# MaximAnalogSignalInterface.net
KiCad netlist of a schematic drawn in Altium Designer
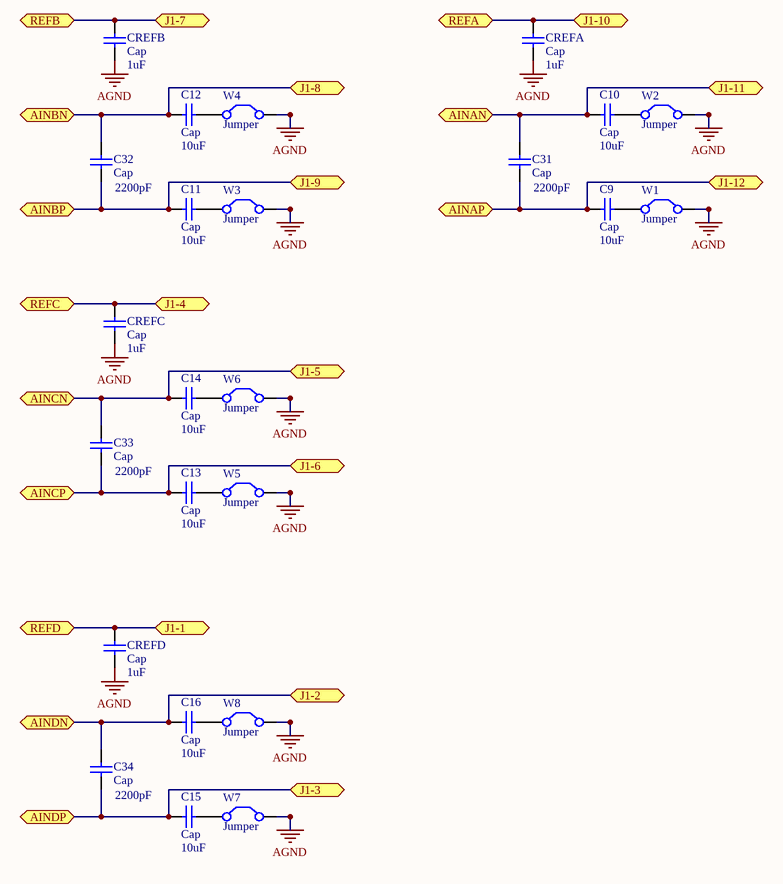
[diagram p0: MaximAnalogSignalInterface.SchDoc]

(export (version "E")
  (design (tool "Eeschema 10.0.6"))
  (components
    (comp (ref "C9")
      (value "Cap")
      (footprint "RAD-0.3")
      (description "Capacitor")
      (fields (field (name "ALTIUM_VALUE") "10uF") (field (name "PUBLISHER") "Altium Limited"))
      (libsource (lib "Miscellaneous Devices") (part "Cap"))
    )
    (comp (ref "C10")
      (value "Cap")
      (footprint "RAD-0.3")
      (description "Capacitor")
      (fields (field (name "ALTIUM_VALUE") "10uF") (field (name "PUBLISHER") "Altium Limited"))
      (libsource (lib "Miscellaneous Devices") (part "Cap"))
    )
    (comp (ref "C11")
      (value "Cap")
      (footprint "RAD-0.3")
      (description "Capacitor")
      (fields (field (name "ALTIUM_VALUE") "10uF") (field (name "PUBLISHER") "Altium Limited"))
      (libsource (lib "Miscellaneous Devices") (part "Cap"))
    )
    (comp (ref "C12")
      (value "Cap")
      (footprint "RAD-0.3")
      (description "Capacitor")
      (fields (field (name "ALTIUM_VALUE") "10uF") (field (name "PUBLISHER") "Altium Limited"))
      (libsource (lib "Miscellaneous Devices") (part "Cap"))
    )
    (comp (ref "C13")
      (value "Cap")
      (footprint "RAD-0.3")
      (description "Capacitor")
      (fields (field (name "ALTIUM_VALUE") "10uF") (field (name "PUBLISHER") "Altium Limited"))
      (libsource (lib "Miscellaneous Devices") (part "Cap"))
    )
    (comp (ref "C14")
      (value "Cap")
      (footprint "RAD-0.3")
      (description "Capacitor")
      (fields (field (name "ALTIUM_VALUE") "10uF") (field (name "PUBLISHER") "Altium Limited"))
      (libsource (lib "Miscellaneous Devices") (part "Cap"))
    )
    (comp (ref "C15")
      (value "Cap")
      (footprint "RAD-0.3")
      (description "Capacitor")
      (fields (field (name "ALTIUM_VALUE") "10uF") (field (name "PUBLISHER") "Altium Limited"))
      (libsource (lib "Miscellaneous Devices") (part "Cap"))
    )
    (comp (ref "C16")
      (value "Cap")
      (footprint "RAD-0.3")
      (description "Capacitor")
      (fields (field (name "ALTIUM_VALUE") "10uF") (field (name "PUBLISHER") "Altium Limited"))
      (libsource (lib "Miscellaneous Devices") (part "Cap"))
    )
    (comp (ref "C31")
      (value "Cap")
      (footprint "RAD-0.3")
      (description "Capacitor")
      (fields (field (name "ALTIUM_VALUE") "2200pF") (field (name "PUBLISHER") "Altium Limited"))
      (libsource (lib "Miscellaneous Devices") (part "Cap"))
    )
    (comp (ref "C32")
      (value "Cap")
      (footprint "RAD-0.3")
      (description "Capacitor")
      (fields (field (name "ALTIUM_VALUE") "2200pF") (field (name "PUBLISHER") "Altium Limited"))
      (libsource (lib "Miscellaneous Devices") (part "Cap"))
    )
    (comp (ref "C33")
      (value "Cap")
      (footprint "RAD-0.3")
      (description "Capacitor")
      (fields (field (name "ALTIUM_VALUE") "2200pF") (field (name "PUBLISHER") "Altium Limited"))
      (libsource (lib "Miscellaneous Devices") (part "Cap"))
    )
    (comp (ref "C34")
      (value "Cap")
      (footprint "RAD-0.3")
      (description "Capacitor")
      (fields (field (name "ALTIUM_VALUE") "2200pF") (field (name "PUBLISHER") "Altium Limited"))
      (libsource (lib "Miscellaneous Devices") (part "Cap"))
    )
    (comp (ref "CREFA")
      (value "Cap")
      (footprint "RAD-0.3")
      (description "Capacitor")
      (fields (field (name "ALTIUM_VALUE") "1uF") (field (name "PUBLISHER") "Altium Limited"))
      (libsource (lib "Miscellaneous Devices") (part "Cap"))
    )
    (comp (ref "CREFB")
      (value "Cap")
      (footprint "RAD-0.3")
      (description "Capacitor")
      (fields (field (name "ALTIUM_VALUE") "1uF") (field (name "PUBLISHER") "Altium Limited"))
      (libsource (lib "Miscellaneous Devices") (part "Cap"))
    )
    (comp (ref "CREFC")
      (value "Cap")
      (footprint "RAD-0.3")
      (description "Capacitor")
      (fields (field (name "ALTIUM_VALUE") "1uF") (field (name "PUBLISHER") "Altium Limited"))
      (libsource (lib "Miscellaneous Devices") (part "Cap"))
    )
    (comp (ref "CREFD")
      (value "Cap")
      (footprint "RAD-0.3")
      (description "Capacitor")
      (fields (field (name "ALTIUM_VALUE") "1uF") (field (name "PUBLISHER") "Altium Limited"))
      (libsource (lib "Miscellaneous Devices") (part "Cap"))
    )
    (comp (ref "W1")
      (value "Jumper")
      (footprint "RAD-0.2")
      (description "Jumper Wire")
      (fields (field (name "PUBLISHER") "Altium Limited"))
      (libsource (lib "Miscellaneous Devices") (part "Jumper"))
    )
    (comp (ref "W2")
      (value "Jumper")
      (footprint "RAD-0.2")
      (description "Jumper Wire")
      (fields (field (name "PUBLISHER") "Altium Limited"))
      (libsource (lib "Miscellaneous Devices") (part "Jumper"))
    )
    (comp (ref "W3")
      (value "Jumper")
      (footprint "RAD-0.2")
      (description "Jumper Wire")
      (fields (field (name "PUBLISHER") "Altium Limited"))
      (libsource (lib "Miscellaneous Devices") (part "Jumper"))
    )
    (comp (ref "W4")
      (value "Jumper")
      (footprint "RAD-0.2")
      (description "Jumper Wire")
      (fields (field (name "PUBLISHER") "Altium Limited"))
      (libsource (lib "Miscellaneous Devices") (part "Jumper"))
    )
    (comp (ref "W5")
      (value "Jumper")
      (footprint "RAD-0.2")
      (description "Jumper Wire")
      (fields (field (name "PUBLISHER") "Altium Limited"))
      (libsource (lib "Miscellaneous Devices") (part "Jumper"))
    )
    (comp (ref "W6")
      (value "Jumper")
      (footprint "RAD-0.2")
      (description "Jumper Wire")
      (fields (field (name "PUBLISHER") "Altium Limited"))
      (libsource (lib "Miscellaneous Devices") (part "Jumper"))
    )
    (comp (ref "W7")
      (value "Jumper")
      (footprint "RAD-0.2")
      (description "Jumper Wire")
      (fields (field (name "PUBLISHER") "Altium Limited"))
      (libsource (lib "Miscellaneous Devices") (part "Jumper"))
    )
    (comp (ref "W8")
      (value "Jumper")
      (footprint "RAD-0.2")
      (description "Jumper Wire")
      (fields (field (name "PUBLISHER") "Altium Limited"))
      (libsource (lib "Miscellaneous Devices") (part "Jumper"))
    )
  )
  (nets
    (net (code "1") (name "/AINAN") (class "Default")
      (node (ref "C10") (pin "2") (pinfunction "2_2") (pintype "passive"))
      (node (ref "C31") (pin "2") (pinfunction "2_2") (pintype "passive"))
    )
    (net (code "2") (name "/AINAP") (class "Default")
      (node (ref "C31") (pin "1") (pinfunction "1_1") (pintype "passive"))
      (node (ref "C9") (pin "2") (pinfunction "2_2") (pintype "passive"))
    )
    (net (code "3") (name "/AINBN") (class "Default")
      (node (ref "C12") (pin "2") (pinfunction "2_2") (pintype "passive"))
      (node (ref "C32") (pin "2") (pinfunction "2_2") (pintype "passive"))
    )
    (net (code "4") (name "/AINBP") (class "Default")
      (node (ref "C11") (pin "2") (pinfunction "2_2") (pintype "passive"))
      (node (ref "C32") (pin "1") (pinfunction "1_1") (pintype "passive"))
    )
    (net (code "5") (name "/AINCN") (class "Default")
      (node (ref "C14") (pin "2") (pinfunction "2_2") (pintype "passive"))
      (node (ref "C33") (pin "2") (pinfunction "2_2") (pintype "passive"))
    )
    (net (code "6") (name "/AINCP") (class "Default")
      (node (ref "C13") (pin "2") (pinfunction "2_2") (pintype "passive"))
      (node (ref "C33") (pin "1") (pinfunction "1_1") (pintype "passive"))
    )
    (net (code "7") (name "/AINDN") (class "Default")
      (node (ref "C16") (pin "2") (pinfunction "2_2") (pintype "passive"))
      (node (ref "C34") (pin "2") (pinfunction "2_2") (pintype "passive"))
    )
    (net (code "8") (name "/AINDP") (class "Default")
      (node (ref "C15") (pin "2") (pinfunction "2_2") (pintype "passive"))
      (node (ref "C34") (pin "1") (pinfunction "1_1") (pintype "passive"))
    )
    (net (code "9") (name "/J1-1") (class "Default")
      (node (ref "CREFD") (pin "2") (pinfunction "2_2") (pintype "passive"))
    )
    (net (code "10") (name "/J1-4") (class "Default")
      (node (ref "CREFC") (pin "2") (pinfunction "2_2") (pintype "passive"))
    )
    (net (code "11") (name "/J1-7") (class "Default")
      (node (ref "CREFB") (pin "2") (pinfunction "2_2") (pintype "passive"))
    )
    (net (code "12") (name "/J1-10") (class "Default")
      (node (ref "CREFA") (pin "2") (pinfunction "2_2") (pintype "passive"))
    )
    (net (code "13") (name "AGND") (class "Default")
      (node (ref "CREFA") (pin "1") (pinfunction "1_1") (pintype "passive"))
      (node (ref "CREFB") (pin "1") (pinfunction "1_1") (pintype "passive"))
      (node (ref "CREFC") (pin "1") (pinfunction "1_1") (pintype "passive"))
      (node (ref "CREFD") (pin "1") (pinfunction "1_1") (pintype "passive"))
      (node (ref "W1") (pin "2") (pinfunction "C2_2") (pintype "passive"))
      (node (ref "W2") (pin "2") (pinfunction "C2_2") (pintype "passive"))
      (node (ref "W3") (pin "2") (pinfunction "C2_2") (pintype "passive"))
      (node (ref "W4") (pin "2") (pinfunction "C2_2") (pintype "passive"))
      (node (ref "W5") (pin "2") (pinfunction "C2_2") (pintype "passive"))
      (node (ref "W6") (pin "2") (pinfunction "C2_2") (pintype "passive"))
      (node (ref "W7") (pin "2") (pinfunction "C2_2") (pintype "passive"))
      (node (ref "W8") (pin "2") (pinfunction "C2_2") (pintype "passive"))
    )
    (net (code "14") (name "Net-(W1-C1)") (class "Default")
      (node (ref "C9") (pin "1") (pinfunction "1_1") (pintype "passive"))
      (node (ref "W1") (pin "1") (pinfunction "C1_1") (pintype "passive"))
    )
    (net (code "15") (name "Net-(W2-C1)") (class "Default")
      (node (ref "C10") (pin "1") (pinfunction "1_1") (pintype "passive"))
      (node (ref "W2") (pin "1") (pinfunction "C1_1") (pintype "passive"))
    )
    (net (code "16") (name "Net-(W3-C1)") (class "Default")
      (node (ref "C11") (pin "1") (pinfunction "1_1") (pintype "passive"))
      (node (ref "W3") (pin "1") (pinfunction "C1_1") (pintype "passive"))
    )
    (net (code "17") (name "Net-(W4-C1)") (class "Default")
      (node (ref "C12") (pin "1") (pinfunction "1_1") (pintype "passive"))
      (node (ref "W4") (pin "1") (pinfunction "C1_1") (pintype "passive"))
    )
    (net (code "18") (name "Net-(W5-C1)") (class "Default")
      (node (ref "C13") (pin "1") (pinfunction "1_1") (pintype "passive"))
      (node (ref "W5") (pin "1") (pinfunction "C1_1") (pintype "passive"))
    )
    (net (code "19") (name "Net-(W6-C1)") (class "Default")
      (node (ref "C14") (pin "1") (pinfunction "1_1") (pintype "passive"))
      (node (ref "W6") (pin "1") (pinfunction "C1_1") (pintype "passive"))
    )
    (net (code "20") (name "Net-(W7-C1)") (class "Default")
      (node (ref "C15") (pin "1") (pinfunction "1_1") (pintype "passive"))
      (node (ref "W7") (pin "1") (pinfunction "C1_1") (pintype "passive"))
    )
    (net (code "21") (name "Net-(W8-C1)") (class "Default")
      (node (ref "C16") (pin "1") (pinfunction "1_1") (pintype "passive"))
      (node (ref "W8") (pin "1") (pinfunction "C1_1") (pintype "passive"))
    )
  )
)
